# Emetteur.net
KiCad netlist of a schematic drawn in Altium Designer
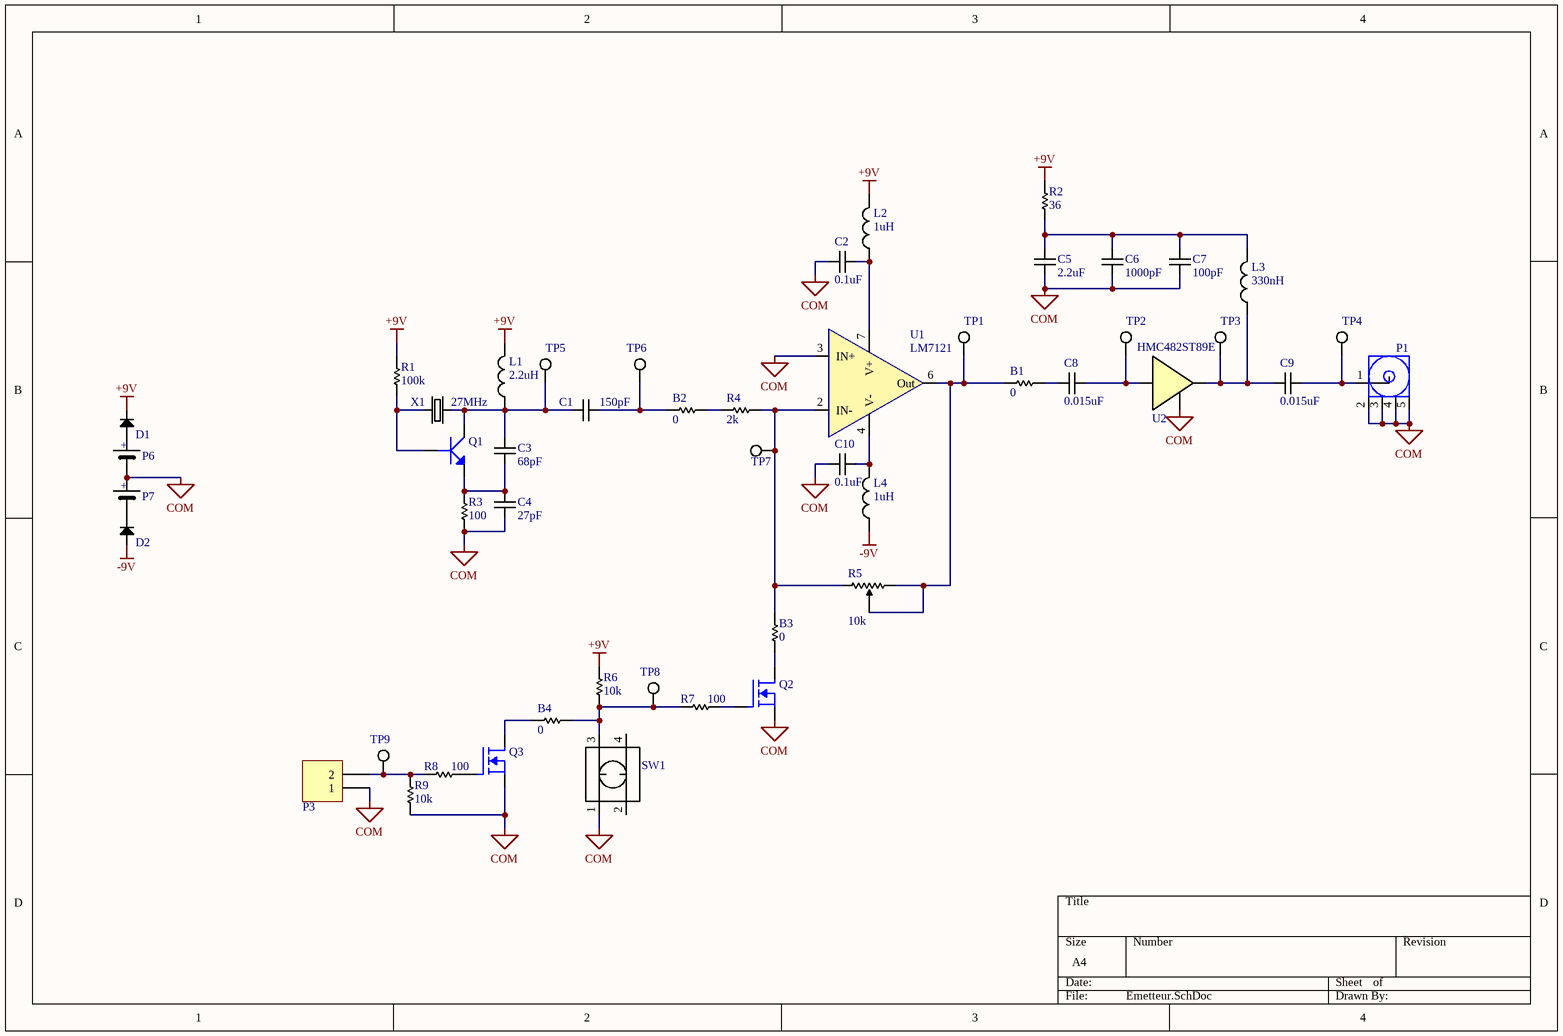
[diagram p0: Emetteur.SchDoc]

(export (version "E")
  (design (tool "Eeschema 10.0.6"))
  (components
    (comp (ref "B1")
      (value "0")
      (footprint "0805 - Resistor")
      (description "RES 0.0 OHM 1/8W JUMP 0805")
      (fields
        (field (name "PART NUMBER") "Jumper-0805")
        (field (name "MANUFACTURER") "Stackpole electronic")
        (field (name "CREATED BY") "Pier-Yves")
      )
      (libsource (lib "local") (part "Res"))
    )
    (comp (ref "B2")
      (value "0")
      (footprint "0805 - Resistor")
      (description "RES 0.0 OHM 1/8W JUMP 0805")
      (fields
        (field (name "PART NUMBER") "Jumper-0805")
        (field (name "MANUFACTURER") "Stackpole electronic")
        (field (name "CREATED BY") "Pier-Yves")
      )
      (libsource (lib "local") (part "Res"))
    )
    (comp (ref "B3")
      (value "0")
      (footprint "0805 - Resistor")
      (description "RES 0.0 OHM 1/8W JUMP 0805")
      (fields
        (field (name "PART NUMBER") "Jumper-0805")
        (field (name "MANUFACTURER") "Stackpole electronic")
        (field (name "CREATED BY") "Pier-Yves")
      )
      (libsource (lib "local") (part "Res"))
    )
    (comp (ref "B4")
      (value "0")
      (footprint "0805 - Resistor")
      (description "RES 0.0 OHM 1/8W JUMP 0805")
      (fields
        (field (name "PART NUMBER") "Jumper-0805")
        (field (name "MANUFACTURER") "Stackpole electronic")
        (field (name "CREATED BY") "Pier-Yves")
      )
      (libsource (lib "local") (part "Res"))
    )
    (comp (ref "C1")
      (value "150pF")
      (footprint "0805 - Cap Non-Polarized")
      (description "CAP CER 150PF 250V 5% NP0 0603")
      (fields
        (field (name "PART NUMBER") "Cap-TDK-CGA-150pF-0805")
        (field (name "MANUFACTURER") "TDK")
        (field (name "CREATED BY") "Pier-Yves")
      )
      (libsource (lib "local") (part "Cap"))
    )
    (comp (ref "C2")
      (value "0.1uF")
      (footprint "0805 - Cap Non-Polarized")
      (description "CAP CER 0.1UF 100V 10% X7R 0805")
      (fields
        (field (name "PART NUMBER") "Cap-TDK-CGA-0.1uF-0805")
        (field (name "MANUFACTURER") "TDK")
        (field (name "CREATED BY") "Pier-Yves")
      )
      (libsource (lib "local") (part "Cap"))
    )
    (comp (ref "C3")
      (value "68pF")
      (footprint "0805 - Cap Non-Polarized")
      (description "CAP CER 68PF 100V 5% NP0 0603")
      (fields
        (field (name "PART NUMBER") "Cap-TDK-CGA-68pF-0805")
        (field (name "MANUFACTURER") "TDK")
        (field (name "CREATED BY") "Pier-Yves")
      )
      (libsource (lib "local") (part "Cap"))
    )
    (comp (ref "C4")
      (value "27pF")
      (footprint "0805 - Cap Non-Polarized")
      (description "CAP CER 27PF 50V 5% NP0 0603")
      (fields
        (field (name "PART NUMBER") "Cap-TDK-CGA-27pF-0805")
        (field (name "MANUFACTURER") "TDK")
        (field (name "CREATED BY") "Pier-Yves")
      )
      (libsource (lib "local") (part "Cap"))
    )
    (comp (ref "C5")
      (value "2.2uF")
      (footprint "0805 - Cap Non-Polarized")
      (description "CAP CER 2.2UF 50V 10% X5R 0805")
      (fields
        (field (name "PART NUMBER") "Cap-Samsung-CL-50V-2.2uF-0805-10%")
        (field (name "MANUFACTURER") "Samsung Electro-Mechanics America, Inc")
        (field (name "CREATED BY") "Pier-Yves")
      )
      (libsource (lib "local") (part "Cap"))
    )
    (comp (ref "C6")
      (value "1000pF")
      (footprint "0805 - Cap Non-Polarized")
      (description "CAP CER 1000PF 100V 5% NP0 0805")
      (fields
        (field (name "PART NUMBER") "Cap-TDK-CGA-1000pF-0805")
        (field (name "MANUFACTURER") "TDK")
        (field (name "CREATED BY") "Pier-Yves")
      )
      (libsource (lib "local") (part "Cap"))
    )
    (comp (ref "C7")
      (value "100pF")
      (footprint "0805 - Cap Non-Polarized")
      (description "CAP CER 100PF 100V 5% NP0 0805")
      (fields
        (field (name "PART NUMBER") "Cap-TDK-CGA-100pF-0805")
        (field (name "MANUFACTURER") "TDK")
        (field (name "CREATED BY") "Pier-Yves")
      )
      (libsource (lib "local") (part "Cap"))
    )
    (comp (ref "C8")
      (value "0.015uF")
      (footprint "0805 - Cap Non-Polarized")
      (description "CAP CER 0.015UF 100V X7R 0805")
      (fields
        (field (name "PART NUMBER") "Cap-TDK-CGA-0.015uF-0805")
        (field (name "MANUFACTURER") "TDK")
        (field (name "CREATED BY") "Pier-Yves")
      )
      (libsource (lib "local") (part "Cap"))
    )
    (comp (ref "C9")
      (value "0.015uF")
      (footprint "0805 - Cap Non-Polarized")
      (description "CAP CER 0.015UF 100V X7R 0805")
      (fields
        (field (name "PART NUMBER") "Cap-TDK-CGA-0.015uF-0805")
        (field (name "MANUFACTURER") "TDK")
        (field (name "CREATED BY") "Pier-Yves")
      )
      (libsource (lib "local") (part "Cap"))
    )
    (comp (ref "C10")
      (value "0.1uF")
      (footprint "0805 - Cap Non-Polarized")
      (description "CAP CER 0.1UF 100V 10% X7R 0805")
      (fields
        (field (name "PART NUMBER") "Cap-TDK-CGA-0.1uF-0805")
        (field (name "MANUFACTURER") "TDK")
        (field (name "CREATED BY") "Pier-Yves")
      )
      (libsource (lib "local") (part "Cap"))
    )
    (comp (ref "D1")
      (value "Diode")
      (footprint "DOS-214AC (SMA)")
      (description "DIODE GEN PURPOSE 1000V 1A SMA")
      (fields
        (field (name "PART NUMBER") "S1M-13-F")
        (field (name "MANUFACTURER") "Diodes Inc.")
        (field (name "CREATED BY") "Pier-Yves")
      )
      (libsource (lib "local") (part "Diode"))
    )
    (comp (ref "D2")
      (value "Diode")
      (footprint "DOS-214AC (SMA)")
      (description "DIODE GEN PURPOSE 1000V 1A SMA")
      (fields
        (field (name "PART NUMBER") "S1M-13-F")
        (field (name "MANUFACTURER") "Diodes Inc.")
        (field (name "CREATED BY") "Pier-Yves")
      )
      (libsource (lib "local") (part "Diode"))
    )
    (comp (ref "L1")
      (value "2.2uH")
      (footprint "1008 - INDUCTOR")
      (description "IND 2200NH 280MA SRF 130MHZ 1008")
      (fields
        (field (name "PART NUMBER") "Murata-LQW2UA-Ind-AirCore-2.2uH")
        (field (name "MANUFACTURER") "Murata Electronics North America")
        (field (name "CREATED BY") "Frederic")
      )
      (libsource (lib "local") (part "Inductor"))
    )
    (comp (ref "L2")
      (value "1uH")
      (footprint "1008 - INDUCTOR")
      (description "IND 1000NH 370MA SRF 290MHZ 1008")
      (fields
        (field (name "PART NUMBER") "Murata-LQW2UA-Ind-AirCore-1uH")
        (field (name "MANUFACTURER") "Murata Electronics North America")
        (field (name "CREATED BY") "Frederic")
      )
      (libsource (lib "local") (part "Inductor"))
    )
    (comp (ref "L3")
      (value "330nH")
      (footprint "1008 - INDUCTOR")
      (description "IND 330NH 450MA SRF 570MHZ 1008")
      (fields
        (field (name "PART NUMBER") "Murata-LQW2UA-Ind-AirCore-330nH")
        (field (name "MANUFACTURER") "Murata Electronics North America")
        (field (name "CREATED BY") "Frederic")
      )
      (libsource (lib "local") (part "Inductor"))
    )
    (comp (ref "L4")
      (value "1uH")
      (footprint "1008 - INDUCTOR")
      (description "IND 1000NH 370MA SRF 290MHZ 1008")
      (fields
        (field (name "PART NUMBER") "Murata-LQW2UA-Ind-AirCore-1uH")
        (field (name "MANUFACTURER") "Murata Electronics North America")
        (field (name "CREATED BY") "Frederic")
      )
      (libsource (lib "local") (part "Inductor"))
    )
    (comp (ref "P1")
      (value "Coax-F")
      (footprint "Coax-BNC-THT-Vertical")
      (description "CONN BNC JACK STR 50 OHM PCB")
      (fields
        (field (name "PART NUMBER") "coax-bnc-tht-vertical")
        (field (name "MANUFACTURER") "TE Connectivity")
        (field (name "CREATED BY") "Pier-Yves")
      )
      (libsource (lib "local") (part "COAX-F"))
    )
    (comp (ref "P3")
      (value "Header 1X2")
      (footprint "Headers - 1x2 - R/A - Lock")
      (fields
        (field (name "PART NUMBER") "Header-0.100-R/A-Lock-1X2")
        (field (name "MANUFACTURER") "Molex Inc.")
        (field (name "PUBLISHER") "Altium Limited")
        (field (name "CREATED BY") "Pier-Yves")
      )
      (libsource (lib "local") (part "Header 1X2"))
    )
    (comp (ref "P6")
      (value "Battery Holder")
      (footprint "Battery Holder - 9V - THT")
      (description "HOLDER BATTERY 9V PC MOUNT")
      (fields
        (field (name "PART NUMBER") "Battery Holder-9V-THT-Open")
        (field (name "MANUFACTURER") "MPD")
        (field (name "CREATED BY") "Pier-Yves")
      )
      (libsource (lib "local") (part "Battery"))
    )
    (comp (ref "P7")
      (value "Battery Holder")
      (footprint "Battery Holder - 9V - THT")
      (description "HOLDER BATTERY 9V PC MOUNT")
      (fields
        (field (name "PART NUMBER") "Battery Holder-9V-THT-Open")
        (field (name "MANUFACTURER") "MPD")
        (field (name "CREATED BY") "Pier-Yves")
      )
      (libsource (lib "local") (part "Battery"))
    )
    (comp (ref "Q1")
      (value "NPN")
      (footprint "SOT23-3")
      (description "TRANS NPN 40V 350MW SMD SOT23-3")
      (fields
        (field (name "PART NUMBER") "MMBT2222A-7-F")
        (field (name "MANUFACTURER") "Diodes Inc.")
        (field (name "CREATED BY") "Pier-Yves")
      )
      (libsource (lib "local") (part "BJT_NPN_BEC"))
    )
    (comp (ref "Q2")
      (value "MOSFET_N")
      (footprint "SOT23-3")
      (description "MosFET Channel-N SOT-23-3 3.3A")
      (fields
        (field (name "PART NUMBER") "2N7002")
        (field (name "MANUFACTURER") "Vishay Siliconix")
        (field (name "CREATED BY") "Pier-Yves")
      )
      (libsource (lib "local") (part "MOSFET_N_GSD"))
    )
    (comp (ref "Q3")
      (value "MOSFET_N")
      (footprint "SOT23-3")
      (description "MosFET Channel-N SOT-23-3 3.3A")
      (fields
        (field (name "PART NUMBER") "2N7002")
        (field (name "MANUFACTURER") "Vishay Siliconix")
        (field (name "CREATED BY") "Pier-Yves")
      )
      (libsource (lib "local") (part "MOSFET_N_GSD"))
    )
    (comp (ref "R1")
      (value "100k")
      (footprint "0805 - Resistor")
      (description "RES 100K OHM 1/8W 5% 0805 SMD")
      (fields
        (field (name "PART NUMBER") "Yagao-RC0805-100k")
        (field (name "MANUFACTURER") "Yagao")
        (field (name "CREATED BY") "Pier-Yves")
      )
      (libsource (lib "local") (part "Res"))
    )
    (comp (ref "R2")
      (value "36")
      (footprint "2512 - Resistor")
      (description "RES 36 OHM 1W 5% 2512 SMD")
      (fields
        (field (name "PART NUMBER") "Rohm-MCR100-36")
        (field (name "MANUFACTURER") "Rohm Semiconductor")
        (field (name "CREATED BY") "Pier-Yves")
      )
      (libsource (lib "local") (part "Res"))
    )
    (comp (ref "R3")
      (value "100")
      (footprint "0805 - Resistor")
      (description "RES 100 OHM 1/8W 5% 0805 SMD")
      (fields
        (field (name "PART NUMBER") "Yagao-RC0805-100")
        (field (name "MANUFACTURER") "Yagao")
        (field (name "CREATED BY") "Pier-Yves")
      )
      (libsource (lib "local") (part "Res"))
    )
    (comp (ref "R4")
      (value "2k")
      (footprint "0805 - Resistor")
      (description "RES 2.0K OHM 1/8W 5% 0805 SMD")
      (fields
        (field (name "PART NUMBER") "Yagao-RC0805-2k")
        (field (name "MANUFACTURER") "Yagao")
        (field (name "CREATED BY") "Pier-Yves")
      )
      (libsource (lib "local") (part "Res"))
    )
    (comp (ref "R5")
      (value "10k")
      (footprint "TT-67Y")
      (description "TRIMMER 10K OHM 0.5W TH")
      (fields
        (field (name "PART NUMBER") "Pot-TT67Y-20Turns-THT-10%-10k")
        (field (name "MANUFACTURER") "TT Electronics")
        (field (name "CREATED BY") "Pier-Yves")
      )
      (libsource (lib "local") (part "Pot_wiper2"))
    )
    (comp (ref "R6")
      (value "10k")
      (footprint "0805 - Resistor")
      (description "RES 10K OHM 1/8W 5% 0805 SMD")
      (fields
        (field (name "PART NUMBER") "Yagao-RC0805-10k")
        (field (name "MANUFACTURER") "Yagao")
        (field (name "CREATED BY") "Pier-Yves")
      )
      (libsource (lib "local") (part "Res"))
    )
    (comp (ref "R7")
      (value "100")
      (footprint "0805 - Resistor")
      (description "RES 100 OHM 1/8W 5% 0805 SMD")
      (fields
        (field (name "PART NUMBER") "Yagao-RC0805-100")
        (field (name "MANUFACTURER") "Yagao")
        (field (name "CREATED BY") "Pier-Yves")
      )
      (libsource (lib "local") (part "Res"))
    )
    (comp (ref "R8")
      (value "100")
      (footprint "0805 - Resistor")
      (description "RES 100 OHM 1/8W 5% 0805 SMD")
      (fields
        (field (name "PART NUMBER") "Yagao-RC0805-100")
        (field (name "MANUFACTURER") "Yagao")
        (field (name "CREATED BY") "Pier-Yves")
      )
      (libsource (lib "local") (part "Res"))
    )
    (comp (ref "R9")
      (value "10k")
      (footprint "0805 - Resistor")
      (description "RES 10K OHM 1/8W 5% 0805 SMD")
      (fields
        (field (name "PART NUMBER") "Yagao-RC0805-10k")
        (field (name "MANUFACTURER") "Yagao")
        (field (name "CREATED BY") "Pier-Yves")
      )
      (libsource (lib "local") (part "Res"))
    )
    (comp (ref "SW1")
      (value "Tact Switch 4")
      (footprint "TE FSMJSMA")
      (description "SWITCH TACTILE SPST-NO 0.05A 12V")
      (fields
        (field (name "PART NUMBER") "TactSwitch-SMD-Vertical-GullWing-6x6")
        (field (name "MANUFACTURER") "TE Connectivity")
        (field (name "CREATED BY") "Pier-Yves")
      )
      (libsource (lib "local") (part "Tact Switch 4"))
    )
    (comp (ref "TP1")
      (value "TP")
      (footprint "TP-THT-Vertical-1")
      (description "TEST POINT PC COMPACT .063\"D BLK")
      (fields
        (field (name "PART NUMBER") "TP-THT-Vertical-1")
        (field (name "MANUFACTURER") "Keystone Electronics")
        (field (name "CREATED BY") "Pier-Yves")
      )
      (libsource (lib "local") (part "TP1"))
    )
    (comp (ref "TP2")
      (value "TP")
      (footprint "TP-THT-Vertical-1")
      (description "TEST POINT PC COMPACT .063\"D BLK")
      (fields
        (field (name "PART NUMBER") "TP-THT-Vertical-1")
        (field (name "MANUFACTURER") "Keystone Electronics")
        (field (name "CREATED BY") "Pier-Yves")
      )
      (libsource (lib "local") (part "TP1"))
    )
    (comp (ref "TP3")
      (value "TP")
      (footprint "TP-THT-Vertical-1")
      (description "TEST POINT PC COMPACT .063\"D BLK")
      (fields
        (field (name "PART NUMBER") "TP-THT-Vertical-1")
        (field (name "MANUFACTURER") "Keystone Electronics")
        (field (name "CREATED BY") "Pier-Yves")
      )
      (libsource (lib "local") (part "TP1"))
    )
    (comp (ref "TP4")
      (value "TP")
      (footprint "TP-THT-Vertical-1")
      (description "TEST POINT PC COMPACT .063\"D BLK")
      (fields
        (field (name "PART NUMBER") "TP-THT-Vertical-1")
        (field (name "MANUFACTURER") "Keystone Electronics")
        (field (name "CREATED BY") "Pier-Yves")
      )
      (libsource (lib "local") (part "TP1"))
    )
    (comp (ref "TP5")
      (value "TP")
      (footprint "TP-THT-Vertical-1")
      (description "TEST POINT PC COMPACT .063\"D BLK")
      (fields
        (field (name "PART NUMBER") "TP-THT-Vertical-1")
        (field (name "MANUFACTURER") "Keystone Electronics")
        (field (name "CREATED BY") "Pier-Yves")
      )
      (libsource (lib "local") (part "TP1"))
    )
    (comp (ref "TP6")
      (value "TP")
      (footprint "TP-THT-Vertical-1")
      (description "TEST POINT PC COMPACT .063\"D BLK")
      (fields
        (field (name "PART NUMBER") "TP-THT-Vertical-1")
        (field (name "MANUFACTURER") "Keystone Electronics")
        (field (name "CREATED BY") "Pier-Yves")
      )
      (libsource (lib "local") (part "TP1"))
    )
    (comp (ref "TP7")
      (value "TP")
      (footprint "TP-THT-Vertical-1")
      (description "TEST POINT PC COMPACT .063\"D BLK")
      (fields
        (field (name "PART NUMBER") "TP-THT-Vertical-1")
        (field (name "MANUFACTURER") "Keystone Electronics")
        (field (name "CREATED BY") "Pier-Yves")
      )
      (libsource (lib "local") (part "TP1"))
    )
    (comp (ref "TP8")
      (value "TP")
      (footprint "TP-THT-Vertical-1")
      (description "TEST POINT PC COMPACT .063\"D BLK")
      (fields
        (field (name "PART NUMBER") "TP-THT-Vertical-1")
        (field (name "MANUFACTURER") "Keystone Electronics")
        (field (name "CREATED BY") "Pier-Yves")
      )
      (libsource (lib "local") (part "TP1"))
    )
    (comp (ref "TP9")
      (value "TP")
      (footprint "TP-THT-Vertical-1")
      (description "TEST POINT PC COMPACT .063\"D BLK")
      (fields
        (field (name "PART NUMBER") "TP-THT-Vertical-1")
        (field (name "MANUFACTURER") "Keystone Electronics")
        (field (name "CREATED BY") "Pier-Yves")
      )
      (libsource (lib "local") (part "TP1"))
    )
    (comp (ref "U1")
      (value "LM7121")
      (footprint "SOIC8 - 0.150")
      (description "IC OPAMP VFB 175MHZ 8SOIC")
      (fields
        (field (name "PART NUMBER") "LM7121-8SOIC")
        (field (name "MANUFACTURER") "Texas Instrument")
        (field (name "CREATED BY") "Pier-Yves")
      )
      (libsource (lib "local") (part "LM7121"))
    )
    (comp (ref "U2")
      (value "Buffer")
      (footprint "SOT-89")
      (description "IC MMIC AMP HBT 5GHZ SOT-89")
      (fields
        (field (name "PART NUMBER") "HMC482ST89E-20dB")
        (field (name "MANUFACTURER") "Hittite Microwave Technology")
        (field (name "MANUFACTURER NO") "HMC482ST89E")
        (field (name "CREATED BY") "Pier-Yves")
      )
      (libsource (lib "local") (part "Buffer_1to3_2Gnd"))
    )
    (comp (ref "X1")
      (value "27MHz")
      (footprint "HC49US")
      (description "CRYSTAL 27MHZ 18PF SMD")
      (fields
        (field (name "PART NUMBER") "TXC-9C-27MHz")
        (field (name "MANUFACTURER") "TXC CORPORATION")
        (field (name "CREATED BY") "Frederic")
      )
      (libsource (lib "local") (part "HC49US"))
    )
  )
  (nets
    (net (code "1") (name "+9V") (class "Default")
      (node (ref "D1") (pin "2") (pinfunction "K_2") (pintype "passive"))
      (node (ref "L1") (pin "2") (pinfunction "2_2") (pintype "passive"))
      (node (ref "L2") (pin "2") (pinfunction "2_2") (pintype "passive"))
      (node (ref "R1") (pin "2") (pinfunction "2_2") (pintype "passive"))
      (node (ref "R2") (pin "1") (pinfunction "1_1") (pintype "passive"))
      (node (ref "R6") (pin "2") (pinfunction "2_2") (pintype "passive"))
    )
    (net (code "2") (name "-9V") (class "Default")
      (node (ref "D2") (pin "1") (pinfunction "A_1") (pintype "passive"))
      (node (ref "L4") (pin "1") (pinfunction "1_1") (pintype "passive"))
    )
    (net (code "3") (name "COM") (class "Default")
      (node (ref "C10") (pin "1") (pinfunction "1_1") (pintype "passive"))
      (node (ref "C2") (pin "1") (pinfunction "1_1") (pintype "passive"))
      (node (ref "C4") (pin "1") (pinfunction "1_1") (pintype "passive"))
      (node (ref "C5") (pin "1") (pinfunction "1_1") (pintype "passive"))
      (node (ref "C6") (pin "1") (pinfunction "1_1") (pintype "passive"))
      (node (ref "C7") (pin "1") (pinfunction "1_1") (pintype "passive"))
      (node (ref "P1") (pin "2") (pinfunction "GND_2") (pintype "passive"))
      (node (ref "P1") (pin "3") (pinfunction "GND_3") (pintype "passive"))
      (node (ref "P1") (pin "4") (pinfunction "GND_4") (pintype "passive"))
      (node (ref "P1") (pin "5") (pinfunction "GND_5") (pintype "passive"))
      (node (ref "P3") (pin "1") (pinfunction "1_1") (pintype "passive"))
      (node (ref "P6") (pin "2") (pinfunction "-_2") (pintype "passive"))
      (node (ref "P7") (pin "1") (pinfunction "+_1") (pintype "passive"))
      (node (ref "Q2") (pin "2") (pinfunction "S_2") (pintype "passive"))
      (node (ref "Q3") (pin "2") (pinfunction "S_2") (pintype "passive"))
      (node (ref "R3") (pin "1") (pinfunction "1_1") (pintype "passive"))
      (node (ref "R9") (pin "1") (pinfunction "1_1") (pintype "passive"))
      (node (ref "SW1") (pin "1") (pinfunction "1_1") (pintype "passive"))
      (node (ref "U1") (pin "3") (pinfunction "IN+_3") (pintype "passive"))
      (node (ref "U2") (pin "2") (pinfunction "Gnd_2") (pintype "passive"))
    )
    (net (code "4") (name "Net-(B1-Pad2)") (class "Default")
      (node (ref "B1") (pin "2") (pinfunction "2_2") (pintype "passive"))
      (node (ref "C8") (pin "1") (pinfunction "1_1") (pintype "passive"))
    )
    (net (code "5") (name "Net-(B2-Pad1)") (class "Default")
      (node (ref "B2") (pin "1") (pinfunction "1_1") (pintype "passive"))
      (node (ref "C1") (pin "2") (pinfunction "2_2") (pintype "passive"))
      (node (ref "TP6") (pin "1") (pinfunction "1_1") (pintype "passive"))
    )
    (net (code "6") (name "Net-(B2-Pad2)") (class "Default")
      (node (ref "B2") (pin "2") (pinfunction "2_2") (pintype "passive"))
      (node (ref "R4") (pin "2") (pinfunction "2_2") (pintype "passive"))
    )
    (net (code "7") (name "Net-(B4-Pad2)") (class "Default")
      (node (ref "B4") (pin "2") (pinfunction "2_2") (pintype "passive"))
      (node (ref "R6") (pin "1") (pinfunction "1_1") (pintype "passive"))
      (node (ref "R7") (pin "1") (pinfunction "1_1") (pintype "passive"))
      (node (ref "SW1") (pin "3") (pinfunction "3_3") (pintype "passive"))
      (node (ref "TP8") (pin "1") (pinfunction "1_1") (pintype "passive"))
    )
    (net (code "8") (name "Net-(C5-Pad2)") (class "Default")
      (node (ref "C5") (pin "2") (pinfunction "2_2") (pintype "passive"))
      (node (ref "C6") (pin "2") (pinfunction "2_2") (pintype "passive"))
      (node (ref "C7") (pin "2") (pinfunction "2_2") (pintype "passive"))
      (node (ref "L3") (pin "2") (pinfunction "2_2") (pintype "passive"))
      (node (ref "R2") (pin "2") (pinfunction "2_2") (pintype "passive"))
    )
    (net (code "9") (name "Net-(D1-A)") (class "Default")
      (node (ref "D1") (pin "1") (pinfunction "A_1") (pintype "passive"))
      (node (ref "P6") (pin "1") (pinfunction "+_1") (pintype "passive"))
    )
    (net (code "10") (name "Net-(D2-K)") (class "Default")
      (node (ref "D2") (pin "2") (pinfunction "K_2") (pintype "passive"))
      (node (ref "P7") (pin "2") (pinfunction "-_2") (pintype "passive"))
    )
    (net (code "11") (name "Net-(P1-Signal)") (class "Default")
      (node (ref "C9") (pin "2") (pinfunction "2_2") (pintype "passive"))
      (node (ref "P1") (pin "1") (pinfunction "Signal_1") (pintype "passive"))
      (node (ref "TP4") (pin "1") (pinfunction "1_1") (pintype "passive"))
    )
    (net (code "12") (name "Net-(P3-Pad2)") (class "Default")
      (node (ref "P3") (pin "2") (pinfunction "2_2") (pintype "passive"))
      (node (ref "R8") (pin "1") (pinfunction "1_1") (pintype "passive"))
      (node (ref "R9") (pin "2") (pinfunction "2_2") (pintype "passive"))
      (node (ref "TP9") (pin "1") (pinfunction "1_1") (pintype "passive"))
    )
    (net (code "13") (name "Net-(Q1-B)") (class "Default")
      (node (ref "Q1") (pin "1") (pinfunction "B_1") (pintype "passive"))
      (node (ref "R1") (pin "1") (pinfunction "1_1") (pintype "passive"))
      (node (ref "X1") (pin "1") (pintype "passive"))
    )
    (net (code "14") (name "Net-(Q1-C)") (class "Default")
      (node (ref "C1") (pin "1") (pinfunction "1_1") (pintype "passive"))
      (node (ref "C3") (pin "2") (pinfunction "2_2") (pintype "passive"))
      (node (ref "L1") (pin "1") (pinfunction "1_1") (pintype "passive"))
      (node (ref "Q1") (pin "3") (pinfunction "C_3") (pintype "passive"))
      (node (ref "TP5") (pin "1") (pinfunction "1_1") (pintype "passive"))
      (node (ref "X1") (pin "2") (pintype "passive"))
    )
    (net (code "15") (name "Net-(Q1-E)") (class "Default")
      (node (ref "C3") (pin "1") (pinfunction "1_1") (pintype "passive"))
      (node (ref "C4") (pin "2") (pinfunction "2_2") (pintype "passive"))
      (node (ref "Q1") (pin "2") (pinfunction "E_2") (pintype "passive"))
      (node (ref "R3") (pin "2") (pinfunction "2_2") (pintype "passive"))
    )
    (net (code "16") (name "Net-(Q2-D)") (class "Default")
      (node (ref "B3") (pin "1") (pinfunction "1_1") (pintype "passive"))
      (node (ref "Q2") (pin "3") (pinfunction "D_3") (pintype "passive"))
    )
    (net (code "17") (name "Net-(Q2-G)") (class "Default")
      (node (ref "Q2") (pin "1") (pinfunction "G_1") (pintype "passive"))
      (node (ref "R7") (pin "2") (pinfunction "2_2") (pintype "passive"))
    )
    (net (code "18") (name "Net-(Q3-D)") (class "Default")
      (node (ref "B4") (pin "1") (pinfunction "1_1") (pintype "passive"))
      (node (ref "Q3") (pin "3") (pinfunction "D_3") (pintype "passive"))
    )
    (net (code "19") (name "Net-(Q3-G)") (class "Default")
      (node (ref "Q3") (pin "1") (pinfunction "G_1") (pintype "passive"))
      (node (ref "R8") (pin "2") (pinfunction "2_2") (pintype "passive"))
    )
    (net (code "20") (name "Net-(R5-Wiper)") (class "Default")
      (node (ref "B1") (pin "1") (pinfunction "1_1") (pintype "passive"))
      (node (ref "R5") (pin "1") (pinfunction "1_1") (pintype "passive"))
      (node (ref "R5") (pin "2") (pinfunction "Wiper_2") (pintype "passive"))
      (node (ref "TP1") (pin "1") (pinfunction "1_1") (pintype "passive"))
      (node (ref "U1") (pin "6") (pinfunction "Out_6") (pintype "passive"))
    )
    (net (code "21") (name "Net-(U1-IN-)") (class "Default")
      (node (ref "B3") (pin "2") (pinfunction "2_2") (pintype "passive"))
      (node (ref "R4") (pin "1") (pinfunction "1_1") (pintype "passive"))
      (node (ref "R5") (pin "3") (pinfunction "3_3") (pintype "passive"))
      (node (ref "TP7") (pin "1") (pinfunction "1_1") (pintype "passive"))
      (node (ref "U1") (pin "2") (pinfunction "IN-_2") (pintype "passive"))
    )
    (net (code "22") (name "Net-(U1-V+)") (class "Default")
      (node (ref "C2") (pin "2") (pinfunction "2_2") (pintype "passive"))
      (node (ref "L2") (pin "1") (pinfunction "1_1") (pintype "passive"))
      (node (ref "U1") (pin "7") (pinfunction "V+_7") (pintype "power_in"))
    )
    (net (code "23") (name "Net-(U1-V-)") (class "Default")
      (node (ref "C10") (pin "2") (pinfunction "2_2") (pintype "passive"))
      (node (ref "L4") (pin "2") (pinfunction "2_2") (pintype "passive"))
      (node (ref "U1") (pin "4") (pinfunction "V-_4") (pintype "power_in"))
    )
    (net (code "24") (name "Net-(U2-In)") (class "Default")
      (node (ref "C8") (pin "2") (pinfunction "2_2") (pintype "passive"))
      (node (ref "TP2") (pin "1") (pinfunction "1_1") (pintype "passive"))
      (node (ref "U2") (pin "1") (pinfunction "In_1") (pintype "passive"))
    )
    (net (code "25") (name "Net-(U2-Out)") (class "Default")
      (node (ref "C9") (pin "1") (pinfunction "1_1") (pintype "passive"))
      (node (ref "L3") (pin "1") (pinfunction "1_1") (pintype "passive"))
      (node (ref "TP3") (pin "1") (pinfunction "1_1") (pintype "passive"))
      (node (ref "U2") (pin "3") (pinfunction "Out_3") (pintype "passive"))
    )
    (net (code "26") (name "unconnected-(SW1-Pad2)") (class "Default")
      (node (ref "SW1") (pin "2") (pinfunction "2_2") (pintype "passive"))
    )
    (net (code "27") (name "unconnected-(SW1-Pad4)") (class "Default")
      (node (ref "SW1") (pin "4") (pinfunction "4_4") (pintype "passive"))
    )
  )
)
